# untitled.net
KiCad netlist of a schematic drawn in EAGLE
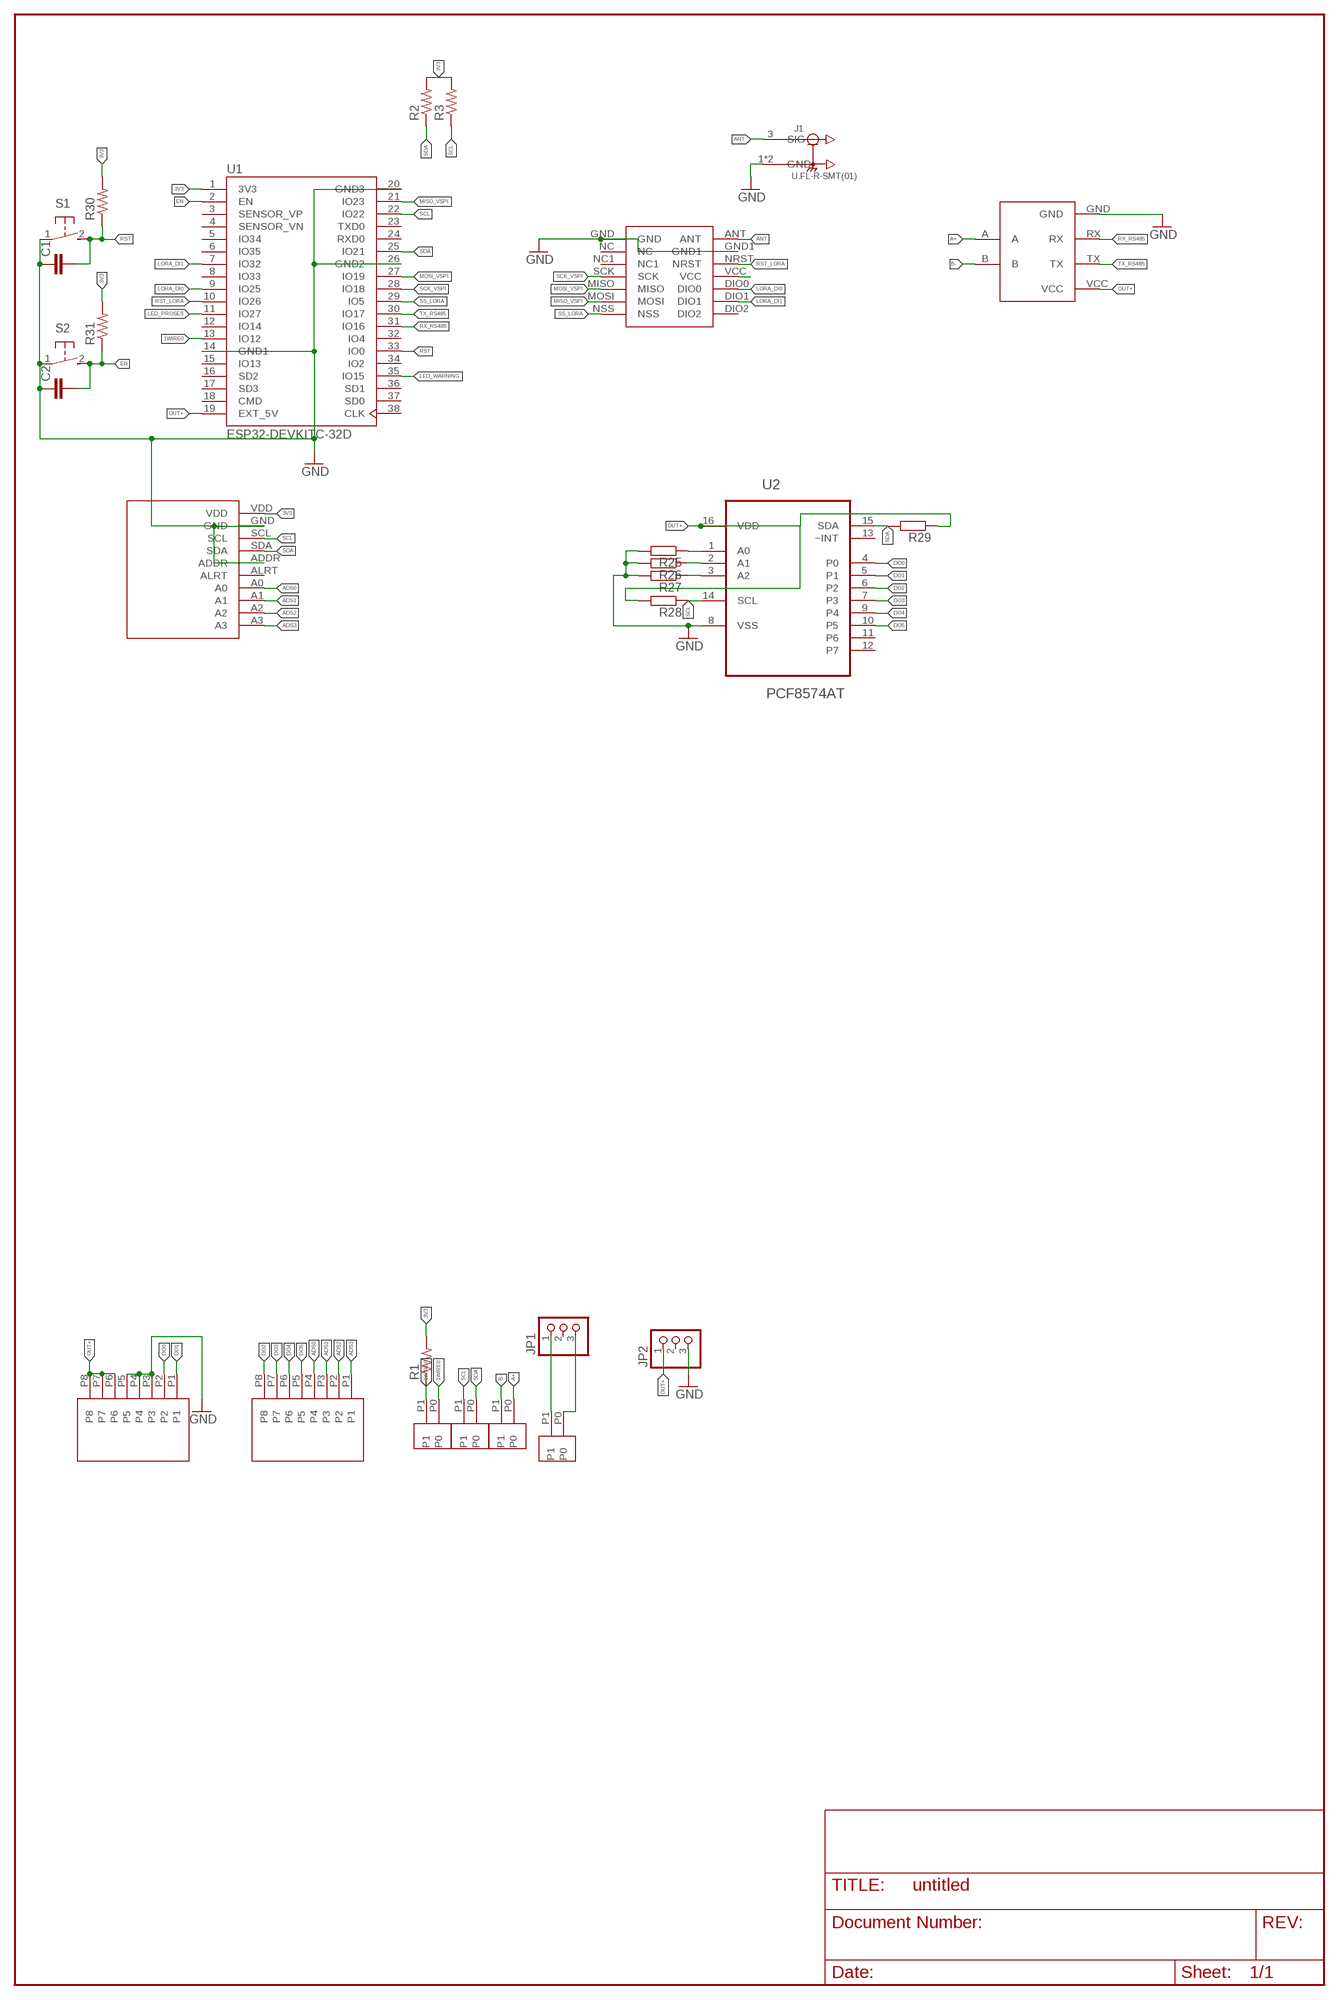
[diagram p0: schematic, sheet 1]

(export (version "E")
  (design (tool "Eeschema 10.0.6"))
  (components
    (comp (ref "ADS1")
      (value "ADS1115")
      (footprint "eagle-import:ADS1115")
      (libsource (lib "eagle-import") (part "ADS1115"))
    )
    (comp (ref "C1")
      (value "C-EUC0805K")
      (footprint "eagle-import:C0805K")
      (libsource (lib "eagle-import") (part "C-EUC0805K"))
    )
    (comp (ref "C2")
      (value "C-EUC0805K")
      (footprint "eagle-import:C0805K")
      (libsource (lib "eagle-import") (part "C-EUC0805K"))
    )
    (comp (ref "CONN2P-3.5PI1")
      (value "CONN2P-3.5PI")
      (footprint "eagle-import:CONN2P-3.5PI")
      (libsource (lib "eagle-import") (part "CONN2P-3.5PI"))
    )
    (comp (ref "CONN2P-3.5PI2")
      (value "CONN2P-3.5PI")
      (footprint "eagle-import:CONN2P-3.5PI")
      (libsource (lib "eagle-import") (part "CONN2P-3.5PI"))
    )
    (comp (ref "CONN2P-3.5PI3")
      (value "CONN2P-3.5PI")
      (footprint "eagle-import:CONN2P-3.5PI")
      (libsource (lib "eagle-import") (part "CONN2P-3.5PI"))
    )
    (comp (ref "CONN2P-3.5PI5")
      (value "CONN2P-3.5PI")
      (footprint "eagle-import:CONN2P-3.5PI")
      (libsource (lib "eagle-import") (part "CONN2P-3.5PI"))
    )
    (comp (ref "CONN3.1")
      (value "CONN3.5")
      (footprint "eagle-import:CONN3.5")
      (libsource (lib "eagle-import") (part "CONN3.5"))
    )
    (comp (ref "CONN3.2")
      (value "CONN3.5")
      (footprint "eagle-import:CONN3.5")
      (libsource (lib "eagle-import") (part "CONN3.5"))
    )
    (comp (ref "J1")
      (value "U.FL-R-SMT(01)")
      (footprint "eagle-import:HRS_U.FL-R-SMT(01)")
      (fields (field (name "MF") "Hirose"))
      (libsource (lib "eagle-import") (part "U.FL-R-SMT(01)"))
    )
    (comp (ref "JP1")
      (value "PINHD-1X3")
      (footprint "eagle-import:1X03")
      (libsource (lib "eagle-import") (part "PINHD-1X3"))
    )
    (comp (ref "JP2")
      (value "PINHD-1X3")
      (footprint "eagle-import:1X03")
      (libsource (lib "eagle-import") (part "PINHD-1X3"))
    )
    (comp (ref "LORA-NICERF-V1")
      (value "LORA-NICERF-V2")
      (footprint "eagle-import:LORA-NICERF-V2")
      (libsource (lib "eagle-import") (part "LORA-NICERF-V2"))
    )
    (comp (ref "R1")
      (value "R-US_M0805")
      (footprint "eagle-import:M0805")
      (libsource (lib "eagle-import") (part "R-US_M0805"))
    )
    (comp (ref "R2")
      (value "R-US_M0805")
      (footprint "eagle-import:M0805")
      (libsource (lib "eagle-import") (part "R-US_M0805"))
    )
    (comp (ref "R3")
      (value "R-US_M0805")
      (footprint "eagle-import:M0805")
      (libsource (lib "eagle-import") (part "R-US_M0805"))
    )
    (comp (ref "R25")
      (value "R-EU_R0805")
      (footprint "eagle-import:R0805")
      (libsource (lib "eagle-import") (part "R-EU_R0805"))
    )
    (comp (ref "R26")
      (value "R-EU_R0805")
      (footprint "eagle-import:R0805")
      (libsource (lib "eagle-import") (part "R-EU_R0805"))
    )
    (comp (ref "R27")
      (value "R-EU_R0805")
      (footprint "eagle-import:R0805")
      (libsource (lib "eagle-import") (part "R-EU_R0805"))
    )
    (comp (ref "R28")
      (value "R-EU_R0805")
      (footprint "eagle-import:R0805")
      (libsource (lib "eagle-import") (part "R-EU_R0805"))
    )
    (comp (ref "R29")
      (value "R-EU_R0805")
      (footprint "eagle-import:R0805")
      (libsource (lib "eagle-import") (part "R-EU_R0805"))
    )
    (comp (ref "R30")
      (value "R-US_M0805")
      (footprint "eagle-import:M0805")
      (libsource (lib "eagle-import") (part "R-US_M0805"))
    )
    (comp (ref "R31")
      (value "R-US_M0805")
      (footprint "eagle-import:M0805")
      (libsource (lib "eagle-import") (part "R-US_M0805"))
    )
    (comp (ref "S1")
      (value "31-XX")
      (footprint "eagle-import:B3F-31XX")
      (fields (field (name "MPN") "B3F-3100"))
      (libsource (lib "eagle-import") (part "31-XX"))
    )
    (comp (ref "S2")
      (value "31-XX")
      (footprint "eagle-import:B3F-31XX")
      (fields (field (name "MPN") "B3F-3100"))
      (libsource (lib "eagle-import") (part "31-XX"))
    )
    (comp (ref "TTL-RS1")
      (value "TTL-RS485")
      (footprint "eagle-import:TTL-RS485")
      (libsource (lib "eagle-import") (part "TTL-RS485"))
    )
    (comp (ref "U1")
      (value "ESP32-DEVKITC-32D")
      (footprint "eagle-import:MODULE_ESP32-DEVKITC-32D")
      (fields (field (name "MF") "Espressif Systems"))
      (libsource (lib "eagle-import") (part "ESP32-DEVKITC-32D"))
    )
    (comp (ref "U2")
      (value "PCF8574AT")
      (footprint "eagle-import:SOIC127P1032X265-16N")
      (fields (field (name "MF") "NXP USA"))
      (libsource (lib "eagle-import") (part "PCF8574AT"))
    )
  )
  (nets
    (net (code "1") (name "1WIRE0") (class "Default")
      (node (ref "CONN2P-3.5PI3") (pin "P0") (pinfunction "P0_P0") (pintype "bidirectional"))
      (node (ref "CONN2P-3.5PI3") (pin "P1") (pinfunction "P1_P1") (pintype "bidirectional"))
      (node (ref "R1") (pin "1") (pinfunction "1_1") (pintype "passive"))
      (node (ref "U1") (pin "13") (pinfunction "IO12_13") (pintype "bidirectional"))
    )
    (net (code "2") (name "3V3") (class "Default")
      (node (ref "ADS1") (pin "VDD") (pinfunction "VDD_VDD") (pintype "bidirectional"))
      (node (ref "R1") (pin "2") (pinfunction "2_2") (pintype "passive"))
      (node (ref "R2") (pin "2") (pinfunction "2_2") (pintype "passive"))
      (node (ref "R3") (pin "2") (pinfunction "2_2") (pintype "passive"))
      (node (ref "R30") (pin "2") (pinfunction "2_2") (pintype "passive"))
      (node (ref "R31") (pin "2") (pinfunction "2_2") (pintype "passive"))
      (node (ref "U1") (pin "1") (pinfunction "3V3_1") (pintype "power_in"))
    )
    (net (code "3") (name "A+") (class "Default")
      (node (ref "CONN2P-3.5PI5") (pin "P0") (pinfunction "P0_P0") (pintype "bidirectional"))
      (node (ref "TTL-RS1") (pin "A") (pinfunction "A_A") (pintype "bidirectional"))
    )
    (net (code "4") (name "ADS0") (class "Default")
      (node (ref "ADS1") (pin "A0") (pinfunction "A0_A0") (pintype "bidirectional"))
      (node (ref "CONN3.2") (pin "P4") (pinfunction "P4_P4") (pintype "bidirectional"))
    )
    (net (code "5") (name "ADS1") (class "Default")
      (node (ref "ADS1") (pin "A1") (pinfunction "A1_A1") (pintype "bidirectional"))
      (node (ref "CONN3.2") (pin "P3") (pinfunction "P3_P3") (pintype "bidirectional"))
    )
    (net (code "6") (name "ADS2") (class "Default")
      (node (ref "ADS1") (pin "A2") (pinfunction "A2_A2") (pintype "bidirectional"))
      (node (ref "CONN3.2") (pin "P2") (pinfunction "P2_P2") (pintype "bidirectional"))
    )
    (net (code "7") (name "ADS3") (class "Default")
      (node (ref "ADS1") (pin "A3") (pinfunction "A3_A3") (pintype "bidirectional"))
      (node (ref "CONN3.2") (pin "P1") (pinfunction "P1_P1") (pintype "bidirectional"))
    )
    (net (code "8") (name "ANT") (class "Default")
      (node (ref "J1") (pin "3") (pinfunction "SIG_3") (pintype "passive"))
      (node (ref "LORA-NICERF-V1") (pin "ANT") (pinfunction "ANT_ANT") (pintype "bidirectional"))
    )
    (net (code "9") (name "B-") (class "Default")
      (node (ref "CONN2P-3.5PI5") (pin "P1") (pinfunction "P1_P1") (pintype "bidirectional"))
      (node (ref "TTL-RS1") (pin "B") (pinfunction "B_B") (pintype "bidirectional"))
    )
    (net (code "10") (name "DO0") (class "Default")
      (node (ref "CONN3.1") (pin "P2") (pinfunction "P2_P2") (pintype "bidirectional"))
      (node (ref "U2") (pin "4") (pinfunction "P0_4") (pintype "bidirectional"))
    )
    (net (code "11") (name "DO1") (class "Default")
      (node (ref "CONN3.1") (pin "P1") (pinfunction "P1_P1") (pintype "bidirectional"))
      (node (ref "U2") (pin "5") (pinfunction "P1_5") (pintype "bidirectional"))
    )
    (net (code "12") (name "DO2") (class "Default")
      (node (ref "CONN3.2") (pin "P8") (pinfunction "P8_P8") (pintype "bidirectional"))
      (node (ref "U2") (pin "6") (pinfunction "P2_6") (pintype "bidirectional"))
    )
    (net (code "13") (name "DO3") (class "Default")
      (node (ref "CONN3.2") (pin "P7") (pinfunction "P7_P7") (pintype "bidirectional"))
      (node (ref "U2") (pin "7") (pinfunction "P3_7") (pintype "bidirectional"))
    )
    (net (code "14") (name "DO4") (class "Default")
      (node (ref "CONN3.2") (pin "P6") (pinfunction "P6_P6") (pintype "bidirectional"))
      (node (ref "U2") (pin "9") (pinfunction "P4_9") (pintype "bidirectional"))
    )
    (net (code "15") (name "DO5") (class "Default")
      (node (ref "CONN3.2") (pin "P5") (pinfunction "P5_P5") (pintype "bidirectional"))
      (node (ref "U2") (pin "10") (pinfunction "P5_10") (pintype "bidirectional"))
    )
    (net (code "16") (name "EN") (class "Default")
      (node (ref "C2") (pin "2") (pinfunction "2_2") (pintype "passive"))
      (node (ref "R31") (pin "1") (pinfunction "1_1") (pintype "passive"))
      (node (ref "S2") (pin "2") (pinfunction "S_2") (pintype "passive"))
      (node (ref "U1") (pin "2") (pinfunction "EN_2") (pintype "input"))
    )
    (net (code "17") (name "GND") (class "Default")
      (node (ref "ADS1") (pin "ADDR") (pinfunction "ADDR_ADDR") (pintype "bidirectional"))
      (node (ref "ADS1") (pin "GND") (pinfunction "GND_GND") (pintype "bidirectional"))
      (node (ref "C1") (pin "1") (pinfunction "1_1") (pintype "passive"))
      (node (ref "C2") (pin "1") (pinfunction "1_1") (pintype "passive"))
      (node (ref "CONN3.1") (pin "P3") (pinfunction "P3_P3") (pintype "bidirectional"))
      (node (ref "CONN3.1") (pin "P4") (pinfunction "P4_P4") (pintype "bidirectional"))
      (node (ref "CONN3.1") (pin "P5") (pinfunction "P5_P5") (pintype "bidirectional"))
      (node (ref "J1") (pin "1") (pinfunction "GND_1") (pintype "passive"))
      (node (ref "J1") (pin "2") (pinfunction "GND_2") (pintype "passive"))
      (node (ref "JP2") (pin "3") (pinfunction "3_3") (pintype "passive"))
      (node (ref "LORA-NICERF-V1") (pin "GND") (pinfunction "GND_GND") (pintype "bidirectional"))
      (node (ref "LORA-NICERF-V1") (pin "GND1") (pinfunction "GND1_GND1") (pintype "bidirectional"))
      (node (ref "R25") (pin "2") (pinfunction "2_2") (pintype "passive"))
      (node (ref "R26") (pin "2") (pinfunction "2_2") (pintype "passive"))
      (node (ref "R27") (pin "2") (pinfunction "2_2") (pintype "passive"))
      (node (ref "S1") (pin "1") (pinfunction "P_1") (pintype "passive"))
      (node (ref "S2") (pin "1") (pinfunction "P_1") (pintype "passive"))
      (node (ref "TTL-RS1") (pin "GND") (pinfunction "GND_GND") (pintype "bidirectional"))
      (node (ref "U1") (pin "14") (pinfunction "GND1_14") (pintype "power_in"))
      (node (ref "U1") (pin "20") (pinfunction "GND3_20") (pintype "power_in"))
      (node (ref "U1") (pin "26") (pinfunction "GND2_26") (pintype "power_in"))
      (node (ref "U2") (pin "8") (pinfunction "VSS_8") (pintype "passive"))
    )
    (net (code "18") (name "LED_PROSES") (class "Default")
      (node (ref "U1") (pin "11") (pinfunction "IO27_11") (pintype "bidirectional"))
    )
    (net (code "19") (name "LED_WARNING") (class "Default")
      (node (ref "U1") (pin "35") (pinfunction "IO15_35") (pintype "bidirectional"))
    )
    (net (code "20") (name "LORA_DI0") (class "Default")
      (node (ref "LORA-NICERF-V1") (pin "DIO0") (pinfunction "DIO0_DIO0") (pintype "bidirectional"))
      (node (ref "U1") (pin "9") (pinfunction "IO25_9") (pintype "bidirectional"))
    )
    (net (code "21") (name "LORA_DI1") (class "Default")
      (node (ref "LORA-NICERF-V1") (pin "DIO1") (pinfunction "DIO1_DIO1") (pintype "bidirectional"))
      (node (ref "U1") (pin "7") (pinfunction "IO32_7") (pintype "bidirectional"))
    )
    (net (code "22") (name "MISO_VSPI") (class "Default")
      (node (ref "LORA-NICERF-V1") (pin "MOSI") (pinfunction "MOSI_MOSI") (pintype "bidirectional"))
      (node (ref "U1") (pin "21") (pinfunction "IO23_21") (pintype "bidirectional"))
    )
    (net (code "23") (name "MOSI_VSPI") (class "Default")
      (node (ref "LORA-NICERF-V1") (pin "MISO") (pinfunction "MISO_MISO") (pintype "bidirectional"))
      (node (ref "U1") (pin "27") (pinfunction "IO19_27") (pintype "bidirectional"))
    )
    (net (code "24") (name "Net-(CONN2P-3.5PI1-PadP0)") (class "Default")
      (node (ref "CONN2P-3.5PI1") (pin "P0") (pinfunction "P0_P0") (pintype "bidirectional"))
      (node (ref "JP1") (pin "3") (pinfunction "3_3") (pintype "passive"))
    )
    (net (code "25") (name "Net-(CONN2P-3.5PI1-PadP1)") (class "Default")
      (node (ref "CONN2P-3.5PI1") (pin "P1") (pinfunction "P1_P1") (pintype "bidirectional"))
      (node (ref "JP1") (pin "1") (pinfunction "1_1") (pintype "passive"))
    )
    (net (code "26") (name "Net-(U2-A0)") (class "Default")
      (node (ref "R25") (pin "1") (pinfunction "1_1") (pintype "passive"))
      (node (ref "U2") (pin "1") (pinfunction "A0_1") (pintype "input"))
    )
    (net (code "27") (name "Net-(U2-A1)") (class "Default")
      (node (ref "R26") (pin "1") (pinfunction "1_1") (pintype "passive"))
      (node (ref "U2") (pin "2") (pinfunction "A1_2") (pintype "input"))
    )
    (net (code "28") (name "Net-(U2-A2)") (class "Default")
      (node (ref "R27") (pin "1") (pinfunction "1_1") (pintype "passive"))
      (node (ref "U2") (pin "3") (pinfunction "A2_3") (pintype "input"))
    )
    (net (code "29") (name "OUT+") (class "Default")
      (node (ref "CONN3.1") (pin "P6") (pinfunction "P6_P6") (pintype "bidirectional"))
      (node (ref "CONN3.1") (pin "P7") (pinfunction "P7_P7") (pintype "bidirectional"))
      (node (ref "CONN3.1") (pin "P8") (pinfunction "P8_P8") (pintype "bidirectional"))
      (node (ref "JP2") (pin "1") (pinfunction "1_1") (pintype "passive"))
      (node (ref "R28") (pin "2") (pinfunction "2_2") (pintype "passive"))
      (node (ref "R29") (pin "1") (pinfunction "1_1") (pintype "passive"))
      (node (ref "TTL-RS1") (pin "VCC") (pinfunction "VCC_VCC") (pintype "bidirectional"))
      (node (ref "U1") (pin "19") (pinfunction "EXT_5V_19") (pintype "power_in"))
      (node (ref "U2") (pin "16") (pinfunction "VDD_16") (pintype "power_in"))
    )
    (net (code "30") (name "RST") (class "Default")
      (node (ref "C1") (pin "2") (pinfunction "2_2") (pintype "passive"))
      (node (ref "R30") (pin "1") (pinfunction "1_1") (pintype "passive"))
      (node (ref "S1") (pin "2") (pinfunction "S_2") (pintype "passive"))
      (node (ref "U1") (pin "33") (pinfunction "IO0_33") (pintype "bidirectional"))
    )
    (net (code "31") (name "RST_LORA") (class "Default")
      (node (ref "LORA-NICERF-V1") (pin "NRST") (pinfunction "NRST_NRST") (pintype "bidirectional"))
      (node (ref "U1") (pin "10") (pinfunction "IO26_10") (pintype "bidirectional"))
    )
    (net (code "32") (name "RX_RS485") (class "Default")
      (node (ref "TTL-RS1") (pin "RX") (pinfunction "RX_RX") (pintype "bidirectional"))
      (node (ref "U1") (pin "31") (pinfunction "IO16_31") (pintype "bidirectional"))
    )
    (net (code "33") (name "SCK_VSPI") (class "Default")
      (node (ref "LORA-NICERF-V1") (pin "SCK") (pinfunction "SCK_SCK") (pintype "bidirectional"))
      (node (ref "U1") (pin "28") (pinfunction "IO18_28") (pintype "bidirectional"))
    )
    (net (code "34") (name "SCL") (class "Default")
      (node (ref "ADS1") (pin "SCL") (pinfunction "SCL_SCL") (pintype "bidirectional"))
      (node (ref "CONN2P-3.5PI2") (pin "P1") (pinfunction "P1_P1") (pintype "bidirectional"))
      (node (ref "R28") (pin "1") (pinfunction "1_1") (pintype "passive"))
      (node (ref "R3") (pin "1") (pinfunction "1_1") (pintype "passive"))
      (node (ref "U1") (pin "22") (pinfunction "IO22_22") (pintype "bidirectional"))
      (node (ref "U2") (pin "14") (pinfunction "SCL_14") (pintype "input"))
    )
    (net (code "35") (name "SDA") (class "Default")
      (node (ref "ADS1") (pin "SDA") (pinfunction "SDA_SDA") (pintype "bidirectional"))
      (node (ref "CONN2P-3.5PI2") (pin "P0") (pinfunction "P0_P0") (pintype "bidirectional"))
      (node (ref "R2") (pin "1") (pinfunction "1_1") (pintype "passive"))
      (node (ref "R29") (pin "2") (pinfunction "2_2") (pintype "passive"))
      (node (ref "U1") (pin "25") (pinfunction "IO21_25") (pintype "bidirectional"))
      (node (ref "U2") (pin "15") (pinfunction "SDA_15") (pintype "bidirectional"))
    )
    (net (code "36") (name "SS_LORA") (class "Default")
      (node (ref "LORA-NICERF-V1") (pin "NSS") (pinfunction "NSS_NSS") (pintype "bidirectional"))
      (node (ref "U1") (pin "29") (pinfunction "IO5_29") (pintype "bidirectional"))
    )
    (net (code "37") (name "TX_RS485") (class "Default")
      (node (ref "TTL-RS1") (pin "TX") (pinfunction "TX_TX") (pintype "bidirectional"))
      (node (ref "U1") (pin "30") (pinfunction "IO17_30") (pintype "bidirectional"))
    )
    (net (code "38") (name "unconnected-(ADS1-PadALRT)") (class "Default")
      (node (ref "ADS1") (pin "ALRT") (pinfunction "ALRT_ALRT") (pintype "bidirectional"))
    )
    (net (code "39") (name "unconnected-(JP1-Pad2)") (class "Default")
      (node (ref "JP1") (pin "2") (pinfunction "2_2") (pintype "passive"))
    )
    (net (code "40") (name "unconnected-(JP2-Pad2)") (class "Default")
      (node (ref "JP2") (pin "2") (pinfunction "2_2") (pintype "passive"))
    )
    (net (code "41") (name "unconnected-(LORA-NICERF-V1-PadDIO2)") (class "Default")
      (node (ref "LORA-NICERF-V1") (pin "DIO2") (pinfunction "DIO2_DIO2") (pintype "bidirectional"))
    )
    (net (code "42") (name "unconnected-(LORA-NICERF-V1-PadNC)") (class "Default")
      (node (ref "LORA-NICERF-V1") (pin "NC") (pinfunction "NC_NC") (pintype "bidirectional"))
    )
    (net (code "43") (name "unconnected-(LORA-NICERF-V1-PadNC1)") (class "Default")
      (node (ref "LORA-NICERF-V1") (pin "NC1") (pinfunction "NC1_NC1") (pintype "bidirectional"))
    )
    (net (code "44") (name "unconnected-(LORA-NICERF-V1-PadVCC)") (class "Default")
      (node (ref "LORA-NICERF-V1") (pin "VCC") (pinfunction "VCC_VCC") (pintype "bidirectional"))
    )
    (net (code "45") (name "unconnected-(U1-CLK-Pad38)") (class "Default")
      (node (ref "U1") (pin "38") (pinfunction "CLK_38") (pintype "input"))
    )
    (net (code "46") (name "unconnected-(U1-CMD-Pad18)") (class "Default")
      (node (ref "U1") (pin "18") (pinfunction "CMD_18") (pintype "bidirectional"))
    )
    (net (code "47") (name "unconnected-(U1-IO2-Pad34)") (class "Default")
      (node (ref "U1") (pin "34") (pinfunction "IO2_34") (pintype "bidirectional"))
    )
    (net (code "48") (name "unconnected-(U1-IO4-Pad32)") (class "Default")
      (node (ref "U1") (pin "32") (pinfunction "IO4_32") (pintype "bidirectional"))
    )
    (net (code "49") (name "unconnected-(U1-IO13-Pad15)") (class "Default")
      (node (ref "U1") (pin "15") (pinfunction "IO13_15") (pintype "bidirectional"))
    )
    (net (code "50") (name "unconnected-(U1-IO14-Pad12)") (class "Default")
      (node (ref "U1") (pin "12") (pinfunction "IO14_12") (pintype "bidirectional"))
    )
    (net (code "51") (name "unconnected-(U1-IO33-Pad8)") (class "Default")
      (node (ref "U1") (pin "8") (pinfunction "IO33_8") (pintype "bidirectional"))
    )
    (net (code "52") (name "unconnected-(U1-IO34-Pad5)") (class "Default")
      (node (ref "U1") (pin "5") (pinfunction "IO34_5") (pintype "bidirectional"))
    )
    (net (code "53") (name "unconnected-(U1-IO35-Pad6)") (class "Default")
      (node (ref "U1") (pin "6") (pinfunction "IO35_6") (pintype "bidirectional"))
    )
    (net (code "54") (name "unconnected-(U1-RXD0-Pad24)") (class "Default")
      (node (ref "U1") (pin "24") (pinfunction "RXD0_24") (pintype "input"))
    )
    (net (code "55") (name "unconnected-(U1-SD0-Pad37)") (class "Default")
      (node (ref "U1") (pin "37") (pinfunction "SD0_37") (pintype "bidirectional"))
    )
    (net (code "56") (name "unconnected-(U1-SD1-Pad36)") (class "Default")
      (node (ref "U1") (pin "36") (pinfunction "SD1_36") (pintype "bidirectional"))
    )
    (net (code "57") (name "unconnected-(U1-SD2-Pad16)") (class "Default")
      (node (ref "U1") (pin "16") (pinfunction "SD2_16") (pintype "bidirectional"))
    )
    (net (code "58") (name "unconnected-(U1-SD3-Pad17)") (class "Default")
      (node (ref "U1") (pin "17") (pinfunction "SD3_17") (pintype "bidirectional"))
    )
    (net (code "59") (name "unconnected-(U1-SENSOR_VN-Pad4)") (class "Default")
      (node (ref "U1") (pin "4") (pinfunction "SENSOR_VN_4") (pintype "input"))
    )
    (net (code "60") (name "unconnected-(U1-SENSOR_VP-Pad3)") (class "Default")
      (node (ref "U1") (pin "3") (pinfunction "SENSOR_VP_3") (pintype "input"))
    )
    (net (code "61") (name "unconnected-(U1-TXD0-Pad23)") (class "Default")
      (node (ref "U1") (pin "23") (pinfunction "TXD0_23") (pintype "output"))
    )
    (net (code "62") (name "unconnected-(U2-P6-Pad11)") (class "Default")
      (node (ref "U2") (pin "11") (pinfunction "P6_11") (pintype "bidirectional"))
    )
    (net (code "63") (name "unconnected-(U2-P7-Pad12)") (class "Default")
      (node (ref "U2") (pin "12") (pinfunction "P7_12") (pintype "bidirectional"))
    )
    (net (code "64") (name "unconnected-(U2-~{INT}-Pad13)") (class "Default")
      (node (ref "U2") (pin "13") (pinfunction "~{INT}_13") (pintype "output"))
    )
  )
)
